# LPCB235_-_ANALOG_CONNECTOR.net
KiCad netlist of a schematic drawn in Altium Designer
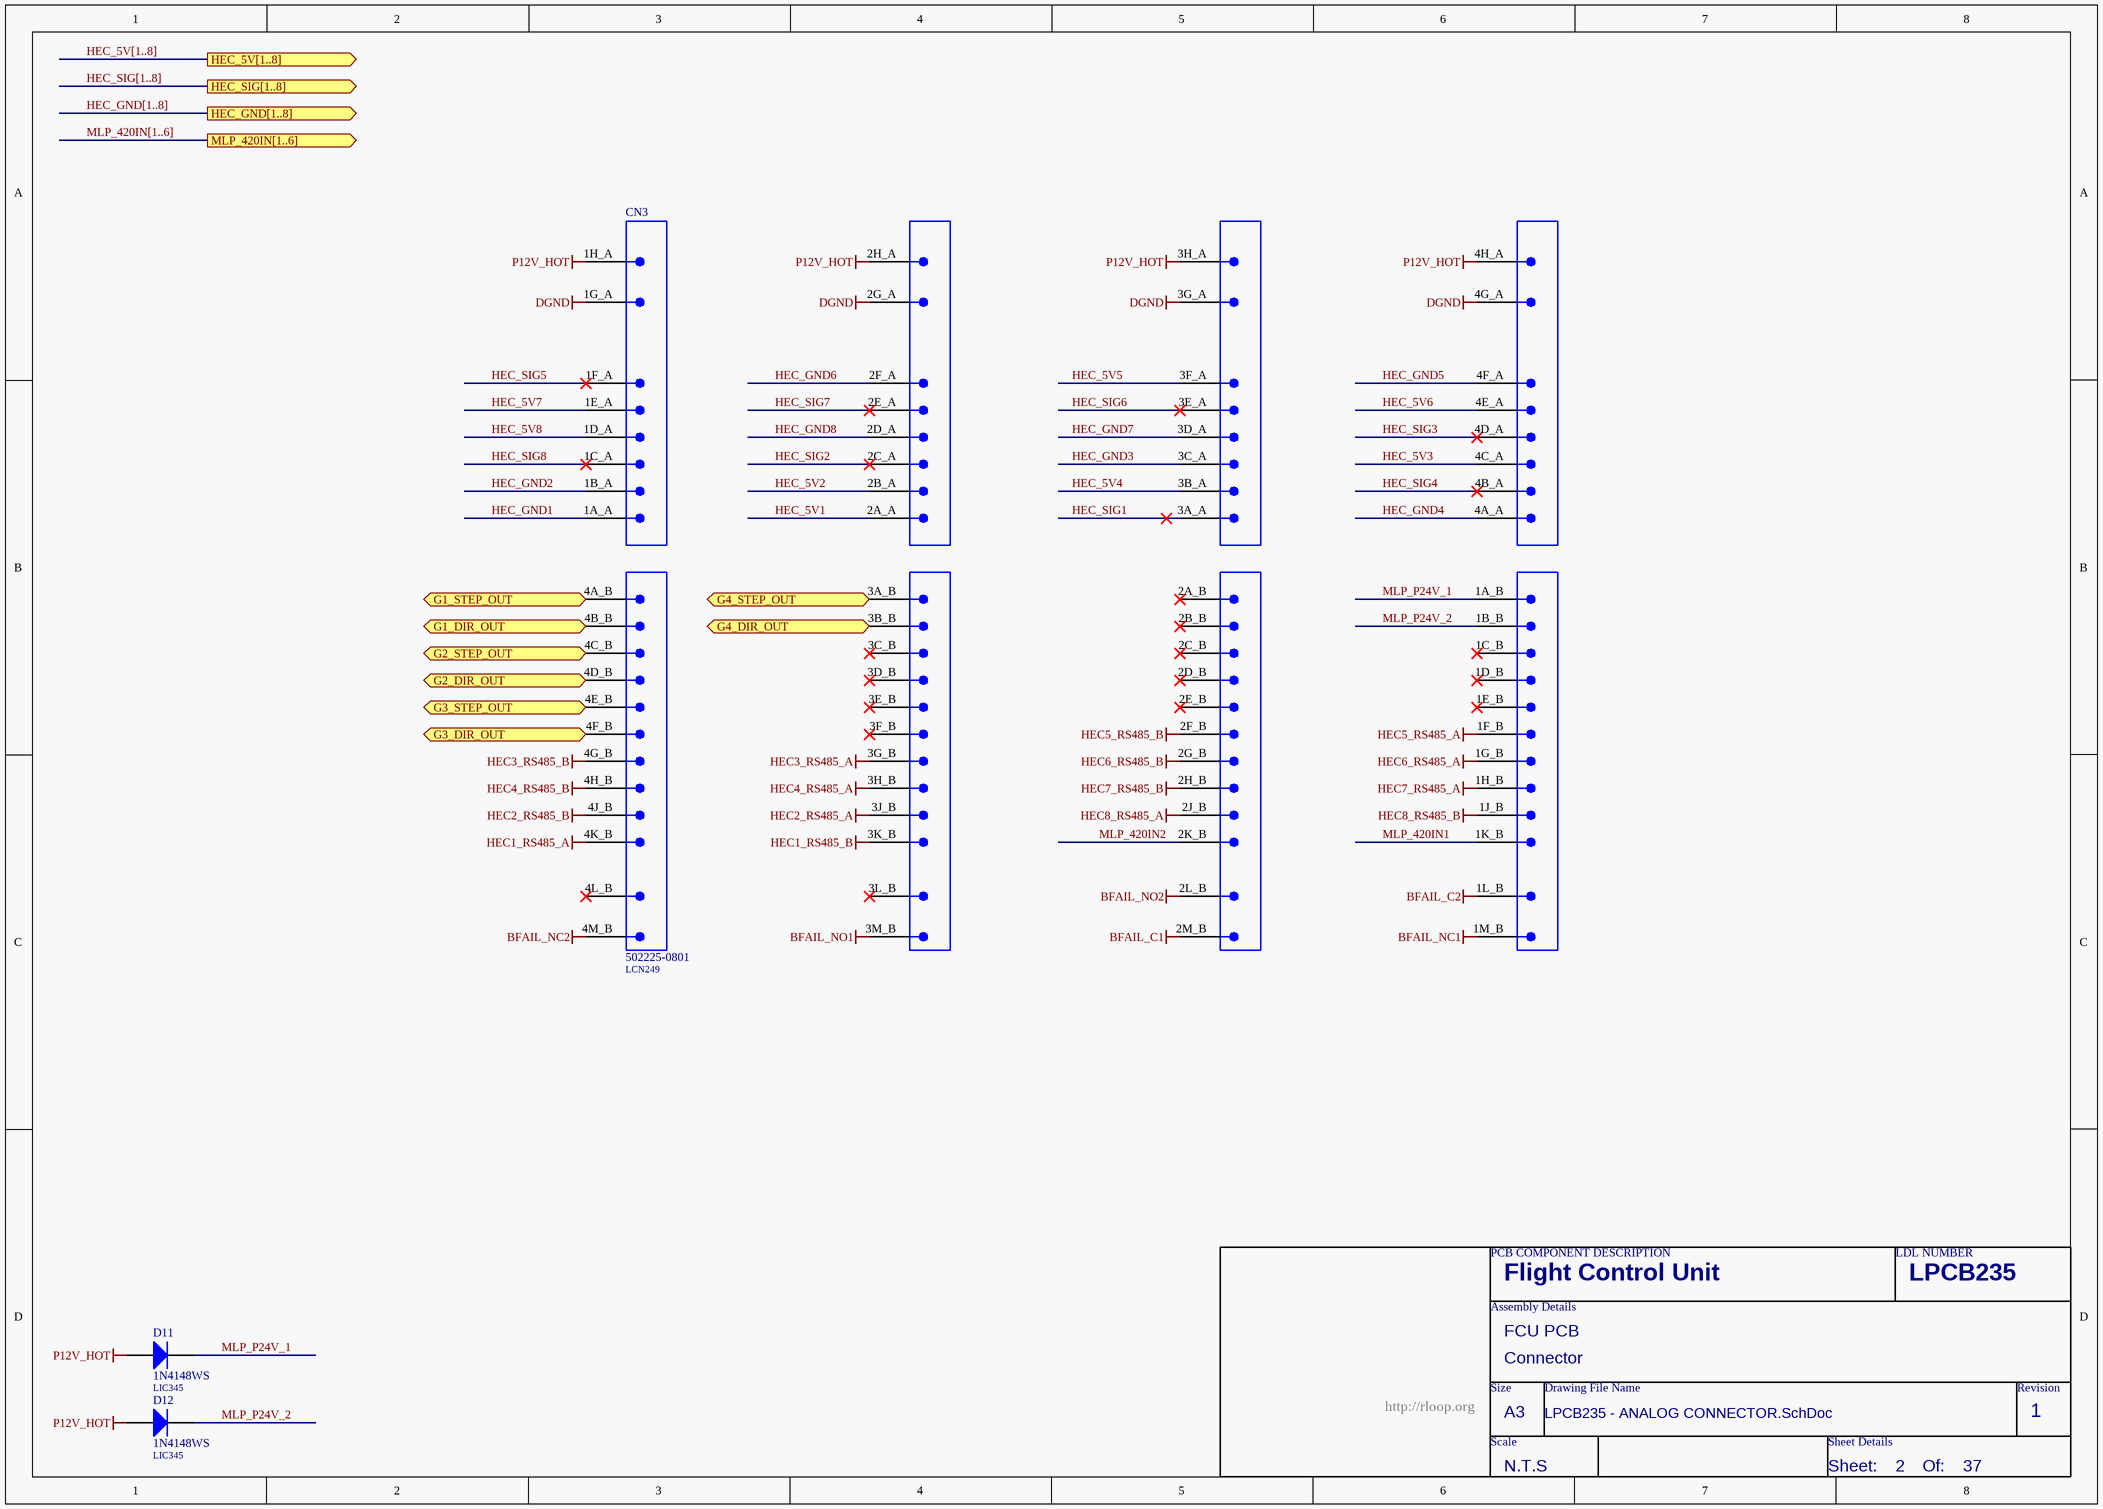
[diagram p0: LPCB235 - ANALOG CONNECTOR.SchDoc]

(export (version "E")
  (design (tool "Eeschema 10.0.6"))
  (components
    (comp (ref "CN3")
      (value "502225-0801")
      (footprint "502225-0801")
      (description "Connector, Molex CMC, Automotive Socket, 80 Circuits, 2 Pockets")
      (fields (field (name "LDL_NUMBER") "LCN249"))
      (libsource (lib "LDL_Connectors") (part "502225-0801"))
    )
    (comp (ref "D11")
      (value "1N4148WS")
      (footprint "LFP001__SOD-323F")
      (description "Diode, Small Signal, SMD SOD-323F [LIC345]")
      (fields (field (name "LDL_NUMBER") "LIC345"))
      (libsource (lib "LDL_Semiconductors") (part "1N4148WS"))
    )
    (comp (ref "D12")
      (value "1N4148WS")
      (footprint "LFP001__SOD-323F")
      (description "Diode, Small Signal, SMD SOD-323F [LIC345]")
      (fields (field (name "LDL_NUMBER") "LIC345"))
      (libsource (lib "LDL_Semiconductors") (part "1N4148WS"))
    )
  )
  (nets
    (net (code "5") (name "/G1_DIR_OUT") (class "Default")
      (node (ref "CN3") (pin "4B_B") (pinfunction "4B_B_4B_B") (pintype "passive"))
    )
    (net (code "6") (name "/G1_STEP_OUT") (class "Default")
      (node (ref "CN3") (pin "4A_B") (pinfunction "4A_B_4A_B") (pintype "passive"))
    )
    (net (code "7") (name "/G2_DIR_OUT") (class "Default")
      (node (ref "CN3") (pin "4D_B") (pinfunction "4D_B_4D_B") (pintype "passive"))
    )
    (net (code "8") (name "/G2_STEP_OUT") (class "Default")
      (node (ref "CN3") (pin "4C_B") (pinfunction "4C_B_4C_B") (pintype "passive"))
    )
    (net (code "9") (name "/G3_DIR_OUT") (class "Default")
      (node (ref "CN3") (pin "4F_B") (pinfunction "4F_B_4F_B") (pintype "passive"))
    )
    (net (code "10") (name "/G3_STEP_OUT") (class "Default")
      (node (ref "CN3") (pin "4E_B") (pinfunction "4E_B_4E_B") (pintype "passive"))
    )
    (net (code "11") (name "/G4_DIR_OUT") (class "Default")
      (node (ref "CN3") (pin "3B_B") (pinfunction "3B_B_3B_B") (pintype "passive"))
    )
    (net (code "12") (name "/G4_STEP_OUT") (class "Default")
      (node (ref "CN3") (pin "3A_B") (pinfunction "3A_B_3A_B") (pintype "passive"))
    )
    (net (code "13") (name "/HEC_5V1") (class "Default")
      (node (ref "CN3") (pin "2A_A") (pinfunction "2A_2A_A") (pintype "passive"))
    )
    (net (code "14") (name "/HEC_5V2") (class "Default")
      (node (ref "CN3") (pin "2B_A") (pinfunction "2B_2B_A") (pintype "passive"))
    )
    (net (code "15") (name "/HEC_5V3") (class "Default")
      (node (ref "CN3") (pin "4C_A") (pinfunction "4C_4C_A") (pintype "passive"))
    )
    (net (code "16") (name "/HEC_5V4") (class "Default")
      (node (ref "CN3") (pin "3B_A") (pinfunction "3B_3B_A") (pintype "passive"))
    )
    (net (code "17") (name "/HEC_5V5") (class "Default")
      (node (ref "CN3") (pin "3F_A") (pinfunction "3F_3F_A") (pintype "passive"))
    )
    (net (code "18") (name "/HEC_5V6") (class "Default")
      (node (ref "CN3") (pin "4E_A") (pinfunction "4E_4E_A") (pintype "passive"))
    )
    (net (code "19") (name "/HEC_5V7") (class "Default")
      (node (ref "CN3") (pin "1E_A") (pinfunction "1E_1E_A") (pintype "passive"))
    )
    (net (code "20") (name "/HEC_5V8") (class "Default")
      (node (ref "CN3") (pin "1D_A") (pinfunction "1D_1D_A") (pintype "passive"))
    )
    (net (code "22") (name "/HEC_GND1") (class "Default")
      (node (ref "CN3") (pin "1A_A") (pinfunction "1A_1A_A") (pintype "passive"))
    )
    (net (code "23") (name "/HEC_GND2") (class "Default")
      (node (ref "CN3") (pin "1B_A") (pinfunction "1B_1B_A") (pintype "passive"))
    )
    (net (code "24") (name "/HEC_GND3") (class "Default")
      (node (ref "CN3") (pin "3C_A") (pinfunction "3C_3C_A") (pintype "passive"))
    )
    (net (code "25") (name "/HEC_GND4") (class "Default")
      (node (ref "CN3") (pin "4A_A") (pinfunction "4A_4A_A") (pintype "passive"))
    )
    (net (code "26") (name "/HEC_GND5") (class "Default")
      (node (ref "CN3") (pin "4F_A") (pinfunction "4F_4F_A") (pintype "passive"))
    )
    (net (code "27") (name "/HEC_GND6") (class "Default")
      (node (ref "CN3") (pin "2F_A") (pinfunction "2F_2F_A") (pintype "passive"))
    )
    (net (code "28") (name "/HEC_GND7") (class "Default")
      (node (ref "CN3") (pin "3D_A") (pinfunction "3D_3D_A") (pintype "passive"))
    )
    (net (code "29") (name "/HEC_GND8") (class "Default")
      (node (ref "CN3") (pin "2D_A") (pinfunction "2D_2D_A") (pintype "passive"))
    )
    (net (code "31") (name "/HEC_SIG1") (class "Default")
      (node (ref "CN3") (pin "3A_A") (pinfunction "3A_3A_A") (pintype "passive"))
    )
    (net (code "32") (name "/HEC_SIG2") (class "Default")
      (node (ref "CN3") (pin "2C_A") (pinfunction "2C_2C_A") (pintype "passive+no_connect"))
    )
    (net (code "33") (name "/HEC_SIG3") (class "Default")
      (node (ref "CN3") (pin "4D_A") (pinfunction "4D_4D_A") (pintype "passive+no_connect"))
    )
    (net (code "34") (name "/HEC_SIG4") (class "Default")
      (node (ref "CN3") (pin "4B_A") (pinfunction "4B_4B_A") (pintype "passive+no_connect"))
    )
    (net (code "35") (name "/HEC_SIG5") (class "Default")
      (node (ref "CN3") (pin "1F_A") (pinfunction "1F_1F_A") (pintype "passive+no_connect"))
    )
    (net (code "36") (name "/HEC_SIG6") (class "Default")
      (node (ref "CN3") (pin "3E_A") (pinfunction "3E_3E_A") (pintype "passive+no_connect"))
    )
    (net (code "37") (name "/HEC_SIG7") (class "Default")
      (node (ref "CN3") (pin "2E_A") (pinfunction "2E_2E_A") (pintype "passive+no_connect"))
    )
    (net (code "38") (name "/HEC_SIG8") (class "Default")
      (node (ref "CN3") (pin "1C_A") (pinfunction "1C_1C_A") (pintype "passive+no_connect"))
    )
    (net (code "40") (name "/MLP_420IN1") (class "Default")
      (node (ref "CN3") (pin "1K_B") (pinfunction "1K_B_1K_B") (pintype "passive"))
    )
    (net (code "41") (name "/MLP_420IN2") (class "Default")
      (node (ref "CN3") (pin "2K_B") (pinfunction "2K_B_2K_B") (pintype "passive"))
    )
    (net (code "43") (name "/MLP_P24V_1") (class "Default")
      (node (ref "CN3") (pin "1A_B") (pinfunction "1A_B_1A_B") (pintype "passive"))
      (node (ref "D11") (pin "1") (pinfunction "K_1") (pintype "passive"))
    )
    (net (code "44") (name "/MLP_P24V_2") (class "Default")
      (node (ref "CN3") (pin "1B_B") (pinfunction "1B_B_1B_B") (pintype "passive"))
      (node (ref "D12") (pin "1") (pinfunction "K_1") (pintype "passive"))
    )
    (net (code "45") (name "BFAIL_C1") (class "Default")
      (node (ref "CN3") (pin "2M_B") (pinfunction "2M_B_2M_B") (pintype "passive"))
    )
    (net (code "46") (name "BFAIL_C2") (class "Default")
      (node (ref "CN3") (pin "1L_B") (pinfunction "1L_B_1L_B") (pintype "passive"))
    )
    (net (code "47") (name "BFAIL_NC1") (class "Default")
      (node (ref "CN3") (pin "1M_B") (pinfunction "1M_B_1M_B") (pintype "passive"))
    )
    (net (code "48") (name "BFAIL_NC2") (class "Default")
      (node (ref "CN3") (pin "4M_B") (pinfunction "4M_B_4M_B") (pintype "passive"))
    )
    (net (code "49") (name "BFAIL_NO1") (class "Default")
      (node (ref "CN3") (pin "3M_B") (pinfunction "3M_B_3M_B") (pintype "passive"))
    )
    (net (code "50") (name "BFAIL_NO2") (class "Default")
      (node (ref "CN3") (pin "2L_B") (pinfunction "2L_B_2L_B") (pintype "passive"))
    )
    (net (code "51") (name "DGND") (class "Default")
      (node (ref "CN3") (pin "1G_A") (pinfunction "1G_1G_A") (pintype "passive"))
      (node (ref "CN3") (pin "2G_A") (pinfunction "2G_2G_A") (pintype "passive"))
      (node (ref "CN3") (pin "3G_A") (pinfunction "3G_3G_A") (pintype "passive"))
      (node (ref "CN3") (pin "4G_A") (pinfunction "4G_4G_A") (pintype "passive"))
    )
    (net (code "52") (name "HEC1_RS485_A") (class "Default")
      (node (ref "CN3") (pin "4K_B") (pinfunction "4K_B_4K_B") (pintype "passive"))
    )
    (net (code "53") (name "HEC1_RS485_B") (class "Default")
      (node (ref "CN3") (pin "3K_B") (pinfunction "3K_B_3K_B") (pintype "passive"))
    )
    (net (code "54") (name "HEC2_RS485_A") (class "Default")
      (node (ref "CN3") (pin "3J_B") (pinfunction "3J_B_3J_B") (pintype "passive"))
    )
    (net (code "55") (name "HEC2_RS485_B") (class "Default")
      (node (ref "CN3") (pin "4J_B") (pinfunction "4J_B_4J_B") (pintype "passive"))
    )
    (net (code "56") (name "HEC3_RS485_A") (class "Default")
      (node (ref "CN3") (pin "3G_B") (pinfunction "3G_B_3G_B") (pintype "passive"))
    )
    (net (code "57") (name "HEC3_RS485_B") (class "Default")
      (node (ref "CN3") (pin "4G_B") (pinfunction "4G_B_4G_B") (pintype "passive"))
    )
    (net (code "58") (name "HEC4_RS485_A") (class "Default")
      (node (ref "CN3") (pin "3H_B") (pinfunction "3H_B_3H_B") (pintype "passive"))
    )
    (net (code "59") (name "HEC4_RS485_B") (class "Default")
      (node (ref "CN3") (pin "4H_B") (pinfunction "4H_B_4H_B") (pintype "passive"))
    )
    (net (code "60") (name "HEC5_RS485_A") (class "Default")
      (node (ref "CN3") (pin "1F_B") (pinfunction "1F_B_1F_B") (pintype "passive"))
    )
    (net (code "61") (name "HEC5_RS485_B") (class "Default")
      (node (ref "CN3") (pin "2F_B") (pinfunction "2F_B_2F_B") (pintype "passive"))
    )
    (net (code "62") (name "HEC6_RS485_A") (class "Default")
      (node (ref "CN3") (pin "1G_B") (pinfunction "1G_B_1G_B") (pintype "passive"))
    )
    (net (code "63") (name "HEC6_RS485_B") (class "Default")
      (node (ref "CN3") (pin "2G_B") (pinfunction "2G_B_2G_B") (pintype "passive"))
    )
    (net (code "64") (name "HEC7_RS485_A") (class "Default")
      (node (ref "CN3") (pin "1H_B") (pinfunction "1H_B_1H_B") (pintype "passive"))
    )
    (net (code "65") (name "HEC7_RS485_B") (class "Default")
      (node (ref "CN3") (pin "2H_B") (pinfunction "2H_B_2H_B") (pintype "passive"))
    )
    (net (code "66") (name "HEC8_RS485_A") (class "Default")
      (node (ref "CN3") (pin "2J_B") (pinfunction "2J_B_2J_B") (pintype "passive"))
    )
    (net (code "67") (name "HEC8_RS485_B") (class "Default")
      (node (ref "CN3") (pin "1J_B") (pinfunction "1J_B_1J_B") (pintype "passive"))
    )
    (net (code "68") (name "P12V_HOT") (class "Default")
      (node (ref "CN3") (pin "1H_A") (pinfunction "1H_1H_A") (pintype "passive"))
      (node (ref "CN3") (pin "2H_A") (pinfunction "2H_2H_A") (pintype "passive"))
      (node (ref "CN3") (pin "3H_A") (pinfunction "3H_3H_A") (pintype "passive"))
      (node (ref "CN3") (pin "4H_A") (pinfunction "4H_4H_A") (pintype "passive"))
      (node (ref "D11") (pin "2") (pinfunction "A_2") (pintype "passive"))
      (node (ref "D12") (pin "2") (pinfunction "A_2") (pintype "passive"))
    )
    (net (code "69") (name "unconnected-(CN3-Pad1C_B)") (class "Default")
      (node (ref "CN3") (pin "1C_B") (pinfunction "1C_B_1C_B") (pintype "passive+no_connect"))
    )
    (net (code "70") (name "unconnected-(CN3-Pad1D_B)") (class "Default")
      (node (ref "CN3") (pin "1D_B") (pinfunction "1D_B_1D_B") (pintype "passive+no_connect"))
    )
    (net (code "71") (name "unconnected-(CN3-Pad1E_B)") (class "Default")
      (node (ref "CN3") (pin "1E_B") (pinfunction "1E_B_1E_B") (pintype "passive+no_connect"))
    )
    (net (code "72") (name "unconnected-(CN3-Pad2A_B)") (class "Default")
      (node (ref "CN3") (pin "2A_B") (pinfunction "2A_B_2A_B") (pintype "passive+no_connect"))
    )
    (net (code "73") (name "unconnected-(CN3-Pad2B_B)") (class "Default")
      (node (ref "CN3") (pin "2B_B") (pinfunction "2B_B_2B_B") (pintype "passive+no_connect"))
    )
    (net (code "74") (name "unconnected-(CN3-Pad2C_B)") (class "Default")
      (node (ref "CN3") (pin "2C_B") (pinfunction "2C_B_2C_B") (pintype "passive+no_connect"))
    )
    (net (code "75") (name "unconnected-(CN3-Pad2D_B)") (class "Default")
      (node (ref "CN3") (pin "2D_B") (pinfunction "2D_B_2D_B") (pintype "passive+no_connect"))
    )
    (net (code "76") (name "unconnected-(CN3-Pad2E_B)") (class "Default")
      (node (ref "CN3") (pin "2E_B") (pinfunction "2E_B_2E_B") (pintype "passive+no_connect"))
    )
    (net (code "77") (name "unconnected-(CN3-Pad3C_B)") (class "Default")
      (node (ref "CN3") (pin "3C_B") (pinfunction "3C_B_3C_B") (pintype "passive+no_connect"))
    )
    (net (code "78") (name "unconnected-(CN3-Pad3D_B)") (class "Default")
      (node (ref "CN3") (pin "3D_B") (pinfunction "3D_B_3D_B") (pintype "passive+no_connect"))
    )
    (net (code "79") (name "unconnected-(CN3-Pad3E_B)") (class "Default")
      (node (ref "CN3") (pin "3E_B") (pinfunction "3E_B_3E_B") (pintype "passive+no_connect"))
    )
    (net (code "80") (name "unconnected-(CN3-Pad3F_B)") (class "Default")
      (node (ref "CN3") (pin "3F_B") (pinfunction "3F_B_3F_B") (pintype "passive+no_connect"))
    )
    (net (code "81") (name "unconnected-(CN3-Pad3L_B)") (class "Default")
      (node (ref "CN3") (pin "3L_B") (pinfunction "3L_B_3L_B") (pintype "passive+no_connect"))
    )
    (net (code "82") (name "unconnected-(CN3-Pad4L_B)") (class "Default")
      (node (ref "CN3") (pin "4L_B") (pinfunction "4L_B_4L_B") (pintype "passive+no_connect"))
    )
  )
)
